# Key_LED_Buzzer.net
KiCad netlist of a schematic drawn in Altium Designer
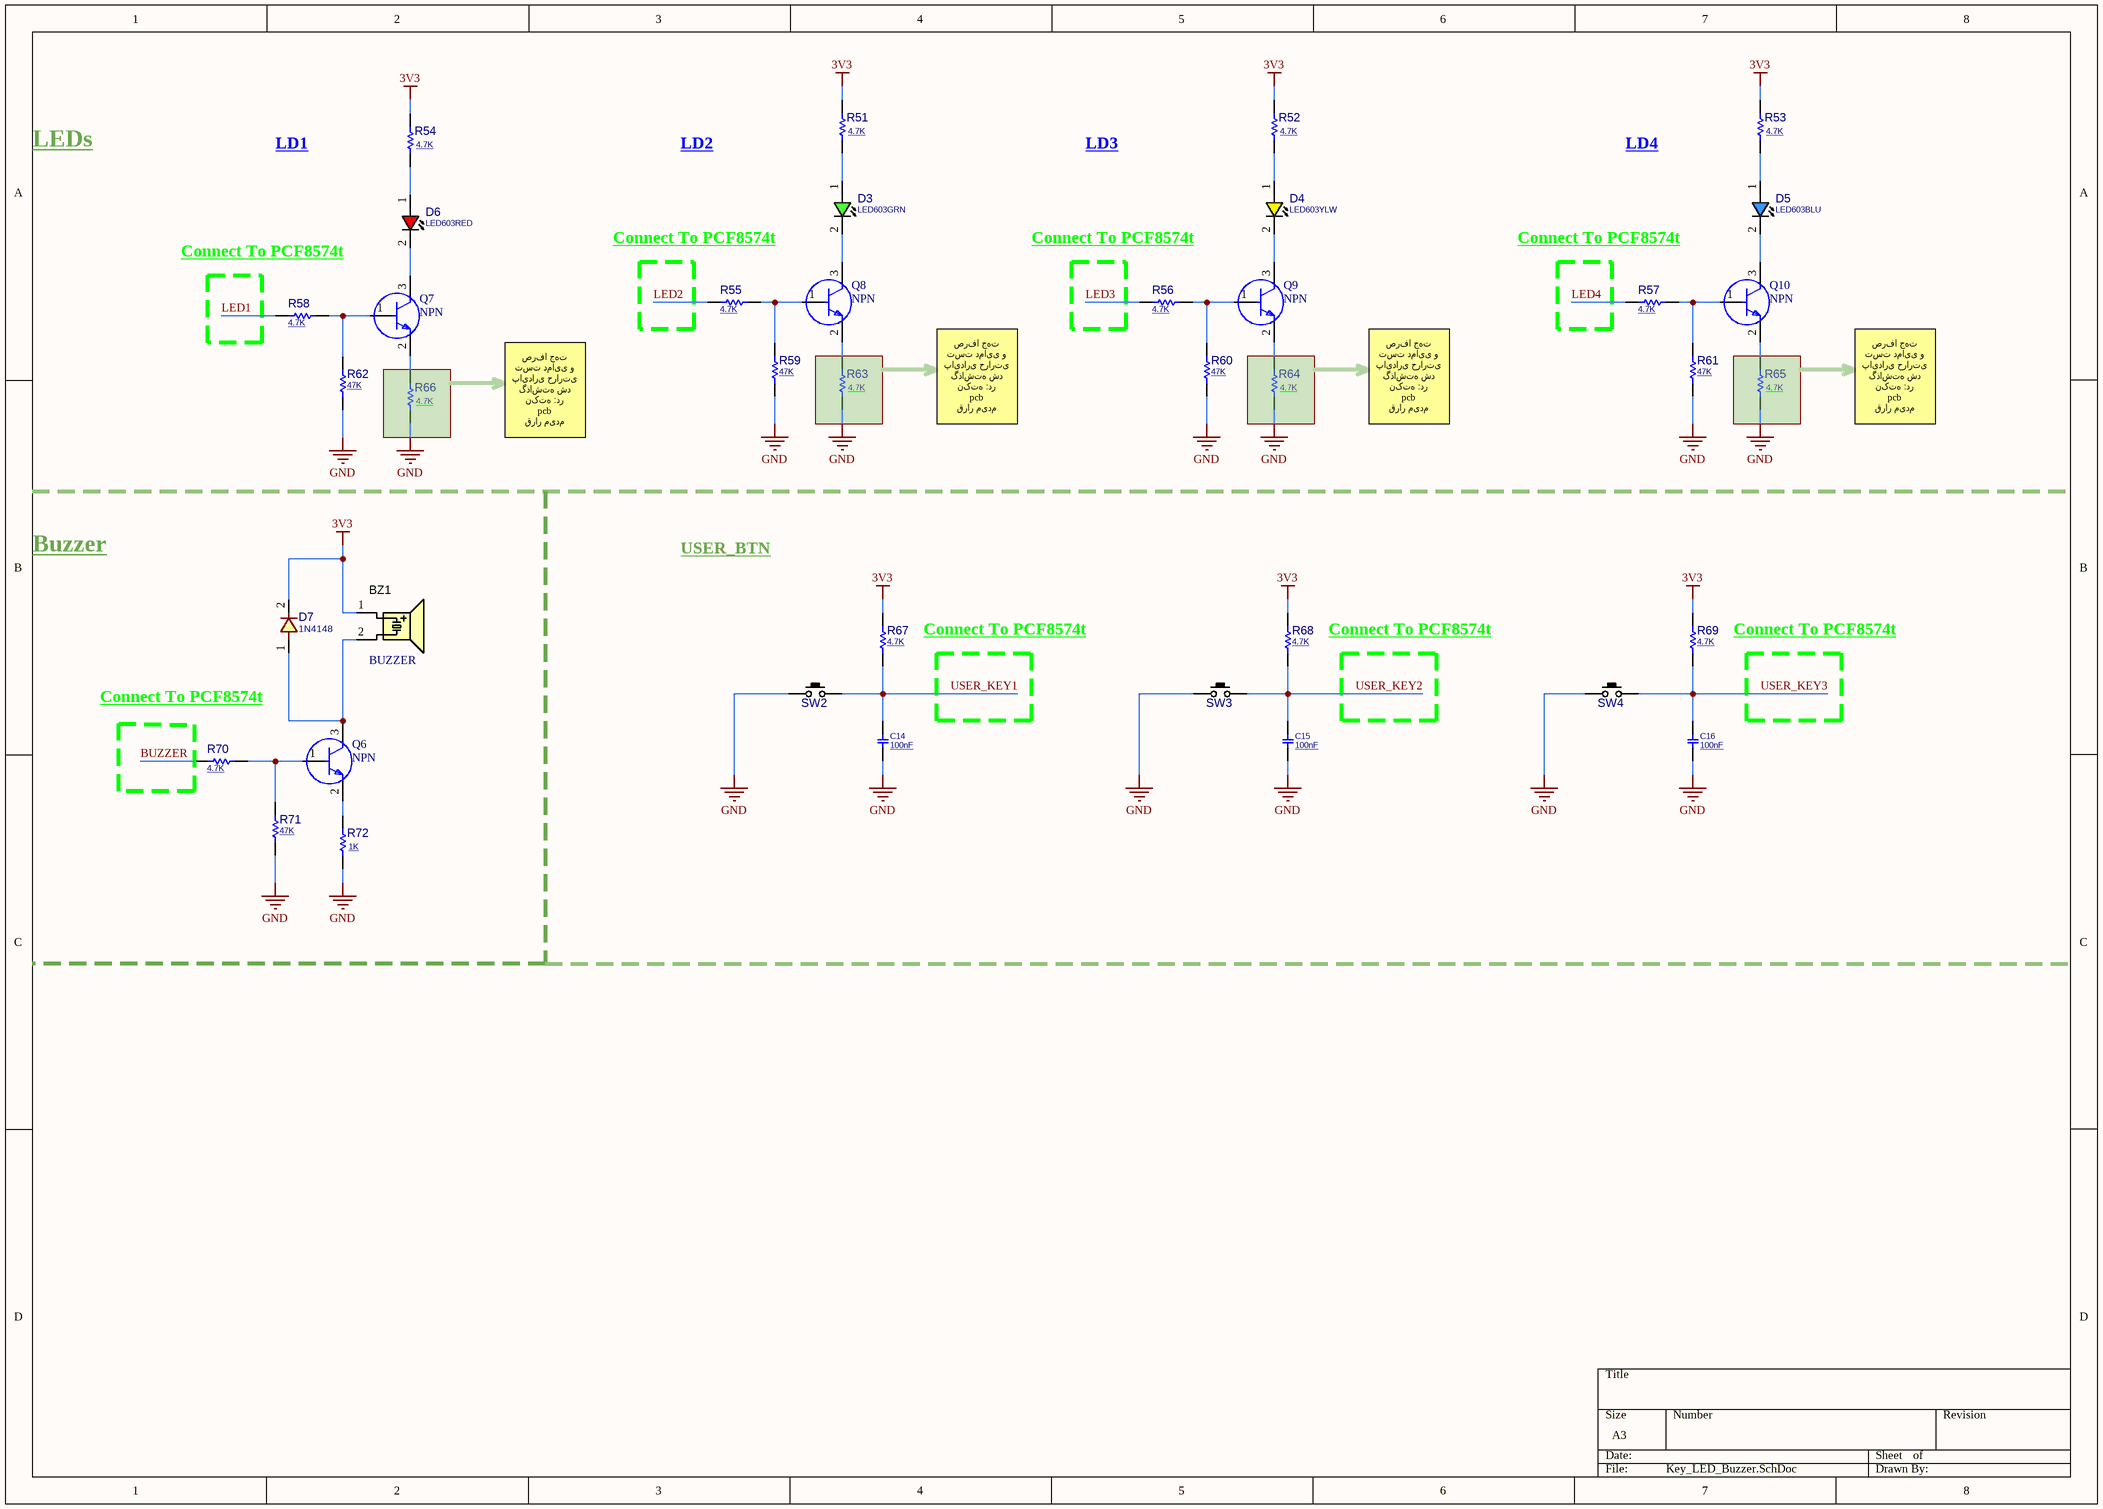
[diagram p0: Key_LED_Buzzer.SchDoc]

(export (version "E")
  (design (tool "Eeschema 10.0.6"))
  (components
    (comp (ref "BZ1")
      (value "BUZZER")
      (footprint "BZ_SMD_S8")
      (description "Buzzer, SMD, sealed 8.5x8.5x3mm LWH , 3Vp")
      (fields (field (name "MANF") "cre-sound") (field (name "MANF_P#") "LET8530BS-03L-2.7-16-R"))
      (libsource (lib "audio_mic_spk") (part "BZ_SMD_8X8X3"))
    )
    (comp (ref "C14")
      (value "100nF")
      (footprint "C0603")
      (description "CAP, MLCC, -F, -V, MATERIAL, -%, 0201")
      (fields (field (name "MANF_P#") "MANF_PART#"))
      (libsource (lib "passive_smd") (part "CAP_SMD_MLCC_0603"))
    )
    (comp (ref "C15")
      (value "100nF")
      (footprint "C0603")
      (description "CAP, MLCC, -F, -V, MATERIAL, -%, 0201")
      (fields (field (name "MANF_P#") "MANF_PART#"))
      (libsource (lib "passive_smd") (part "CAP_SMD_MLCC_0603"))
    )
    (comp (ref "C16")
      (value "100nF")
      (footprint "C0603")
      (description "CAP, MLCC, -F, -V, MATERIAL, -%, 0201")
      (fields (field (name "MANF_P#") "MANF_PART#"))
      (libsource (lib "passive_smd") (part "CAP_SMD_MLCC_0603"))
    )
    (comp (ref "D3")
      (value "LED603GRN")
      (footprint "LED0603GRN")
      (description "LED, SMD, 0603, GREEN")
      (fields (field (name "MANF") "Kingbright") (field (name "MANF_P#") "APT1608SGC"))
      (libsource (lib "led(diode)") (part "LED_SMD_0603_GRN"))
    )
    (comp (ref "D4")
      (value "LED603YLW")
      (footprint "LED0603YLW")
      (description "LED, SMD, 0603, YELLOW")
      (fields (field (name "MANF") "MANF") (field (name "MANF_P#") "MANF_PART#"))
      (libsource (lib "led(diode)") (part "LED_SMD_0603_YLW"))
    )
    (comp (ref "D5")
      (value "LED603BLU")
      (footprint "LED0603BLU")
      (description "LED, SMD, 0603, BLUE")
      (fields (field (name "MANF") "MANF") (field (name "MANF_P#") "MANF_PART#"))
      (libsource (lib "led(diode)") (part "LED_SMD_0603_BLU"))
    )
    (comp (ref "D6")
      (value "LED603RED")
      (footprint "LED0603RED")
      (description "LED, SMD, 0603, RED")
      (fields (field (name "MANF") "MANF") (field (name "MANF_P#") "MANF_PART#"))
      (libsource (lib "led(diode)") (part "LED_SMD_0603_RED"))
    )
    (comp (ref "D7")
      (value "1N4148")
      (footprint "D_SOD80")
      (description "DIODE, FAST SWTICHING, 0.3A, 0.5W")
      (fields (field (name "MANF") "MANF"))
      (libsource (lib "diode") (part "DIODE_SMD_1N4148_SOD80"))
    )
    (comp (ref "Q6")
      (value "NPN")
      (footprint "FP-SOT23-IPC_A")
      (libsource (lib "NPN-SOT-23") (part "CMP-2000-04931-2"))
    )
    (comp (ref "Q7")
      (value "NPN")
      (footprint "FP-SOT23-IPC_A")
      (libsource (lib "NPN-SOT-23") (part "CMP-2000-04931-2"))
    )
    (comp (ref "Q8")
      (value "NPN")
      (footprint "FP-SOT23-IPC_A")
      (libsource (lib "NPN-SOT-23") (part "CMP-2000-04931-2"))
    )
    (comp (ref "Q9")
      (value "NPN")
      (footprint "FP-SOT23-IPC_A")
      (libsource (lib "NPN-SOT-23") (part "CMP-2000-04931-2"))
    )
    (comp (ref "Q10")
      (value "NPN")
      (footprint "FP-SOT23-IPC_A")
      (libsource (lib "NPN-SOT-23") (part "CMP-2000-04931-2"))
    )
    (comp (ref "R51")
      (value "4.7K")
      (footprint "R0603")
      (description "RESISTOR, SMD")
      (libsource (lib "passive_smd") (part "RES_SMD"))
    )
    (comp (ref "R52")
      (value "4.7K")
      (footprint "R0603")
      (description "RESISTOR, SMD")
      (libsource (lib "passive_smd") (part "RES_SMD"))
    )
    (comp (ref "R53")
      (value "4.7K")
      (footprint "R0603")
      (description "RESISTOR, SMD")
      (libsource (lib "passive_smd") (part "RES_SMD"))
    )
    (comp (ref "R54")
      (value "4.7K")
      (footprint "R0603")
      (description "RESISTOR, SMD")
      (libsource (lib "passive_smd") (part "RES_SMD"))
    )
    (comp (ref "R55")
      (value "4.7K")
      (footprint "R0603")
      (description "RESISTOR, SMD")
      (libsource (lib "passive_smd") (part "RES_SMD"))
    )
    (comp (ref "R56")
      (value "4.7K")
      (footprint "R0603")
      (description "RESISTOR, SMD")
      (libsource (lib "passive_smd") (part "RES_SMD"))
    )
    (comp (ref "R57")
      (value "4.7K")
      (footprint "R0603")
      (description "RESISTOR, SMD")
      (libsource (lib "passive_smd") (part "RES_SMD"))
    )
    (comp (ref "R58")
      (value "4.7K")
      (footprint "R0603")
      (description "RESISTOR, SMD")
      (libsource (lib "passive_smd") (part "RES_SMD"))
    )
    (comp (ref "R59")
      (value "47K")
      (footprint "R0603")
      (description "RESISTOR, SMD")
      (libsource (lib "passive_smd") (part "RES_SMD"))
    )
    (comp (ref "R60")
      (value "47K")
      (footprint "R0603")
      (description "RESISTOR, SMD")
      (libsource (lib "passive_smd") (part "RES_SMD"))
    )
    (comp (ref "R61")
      (value "47K")
      (footprint "R0603")
      (description "RESISTOR, SMD")
      (libsource (lib "passive_smd") (part "RES_SMD"))
    )
    (comp (ref "R62")
      (value "47K")
      (footprint "R0603")
      (description "RESISTOR, SMD")
      (libsource (lib "passive_smd") (part "RES_SMD"))
    )
    (comp (ref "R63")
      (value "4.7K")
      (footprint "R0603")
      (description "RESISTOR, SMD")
      (libsource (lib "passive_smd") (part "RES_SMD"))
    )
    (comp (ref "R64")
      (value "4.7K")
      (footprint "R0603")
      (description "RESISTOR, SMD")
      (libsource (lib "passive_smd") (part "RES_SMD"))
    )
    (comp (ref "R65")
      (value "4.7K")
      (footprint "R0603")
      (description "RESISTOR, SMD")
      (libsource (lib "passive_smd") (part "RES_SMD"))
    )
    (comp (ref "R66")
      (value "4.7K")
      (footprint "R0603")
      (description "RESISTOR, SMD")
      (libsource (lib "passive_smd") (part "RES_SMD"))
    )
    (comp (ref "R67")
      (value "4.7K")
      (footprint "R0603")
      (description "RESISTOR, SMD")
      (libsource (lib "passive_smd") (part "RES_SMD"))
    )
    (comp (ref "R68")
      (value "4.7K")
      (footprint "R0603")
      (description "RESISTOR, SMD")
      (libsource (lib "passive_smd") (part "RES_SMD"))
    )
    (comp (ref "R69")
      (value "4.7K")
      (footprint "R0603")
      (description "RESISTOR, SMD")
      (libsource (lib "passive_smd") (part "RES_SMD"))
    )
    (comp (ref "R70")
      (value "4.7K")
      (footprint "R0603")
      (description "RESISTOR, SMD")
      (libsource (lib "passive_smd") (part "RES_SMD"))
    )
    (comp (ref "R71")
      (value "47K")
      (footprint "R0603")
      (description "RESISTOR, SMD")
      (libsource (lib "passive_smd") (part "RES_SMD"))
    )
    (comp (ref "R72")
      (value "1K")
      (footprint "R0603")
      (description "RESISTOR, SMD")
      (libsource (lib "passive_smd") (part "RES_SMD"))
    )
    (comp (ref "SW2")
      (value "PUSHBUTTON")
      (footprint "SWPBS_SPST_6X3X5")
      (description "SWITCH, PUSH BUTTON, TACTILE, SMD, SPST, 6X3.5X5mm")
      (fields (field (name "MANF") "ALPS") (field (name "MANF_P#") "SKQMBBE010"))
      (libsource (lib "switch_tact_PUSHB") (part "SWPBS_SPST_6X3X5"))
    )
    (comp (ref "SW3")
      (value "PUSHBUTTON")
      (footprint "SWPBS_SPST_6X3X5")
      (description "SWITCH, PUSH BUTTON, TACTILE, SMD, SPST, 6X3.5X5mm")
      (fields (field (name "MANF") "ALPS") (field (name "MANF_P#") "SKQMBBE010"))
      (libsource (lib "switch_tact_PUSHB") (part "SWPBS_SPST_6X3X5"))
    )
    (comp (ref "SW4")
      (value "PUSHBUTTON")
      (footprint "SWPBS_SPST_6X3X5")
      (description "SWITCH, PUSH BUTTON, TACTILE, SMD, SPST, 6X3.5X5mm")
      (fields (field (name "MANF") "ALPS") (field (name "MANF_P#") "SKQMBBE010"))
      (libsource (lib "switch_tact_PUSHB") (part "SWPBS_SPST_6X3X5"))
    )
  )
  (nets
    (net (code "1") (name "/BUZZER") (class "Default")
      (node (ref "R70") (pin "2") (pinfunction "2_2") (pintype "passive"))
    )
    (net (code "2") (name "/LED1") (class "Default")
      (node (ref "R58") (pin "2") (pinfunction "2_2") (pintype "passive"))
    )
    (net (code "3") (name "/LED2") (class "Default")
      (node (ref "R55") (pin "2") (pinfunction "2_2") (pintype "passive"))
    )
    (net (code "4") (name "/LED3") (class "Default")
      (node (ref "R56") (pin "2") (pinfunction "2_2") (pintype "passive"))
    )
    (net (code "5") (name "/LED4") (class "Default")
      (node (ref "R57") (pin "2") (pinfunction "2_2") (pintype "passive"))
    )
    (net (code "6") (name "/USER_KEY1") (class "Default")
      (node (ref "C14") (pin "2") (pinfunction "2_2") (pintype "passive"))
      (node (ref "R67") (pin "2") (pinfunction "2_2") (pintype "passive"))
      (node (ref "SW2") (pin "2") (pinfunction "P3_2") (pintype "passive"))
    )
    (net (code "7") (name "/USER_KEY2") (class "Default")
      (node (ref "C15") (pin "2") (pinfunction "2_2") (pintype "passive"))
      (node (ref "R68") (pin "2") (pinfunction "2_2") (pintype "passive"))
      (node (ref "SW3") (pin "2") (pinfunction "P3_2") (pintype "passive"))
    )
    (net (code "8") (name "/USER_KEY3") (class "Default")
      (node (ref "C16") (pin "2") (pinfunction "2_2") (pintype "passive"))
      (node (ref "R69") (pin "2") (pinfunction "2_2") (pintype "passive"))
      (node (ref "SW4") (pin "2") (pinfunction "P3_2") (pintype "passive"))
    )
    (net (code "9") (name "3V3") (class "Default")
      (node (ref "BZ1") (pin "1") (pinfunction "A_1") (pintype "passive"))
      (node (ref "D7") (pin "2") (pinfunction "2_2") (pintype "passive"))
      (node (ref "R51") (pin "2") (pinfunction "2_2") (pintype "passive"))
      (node (ref "R52") (pin "2") (pinfunction "2_2") (pintype "passive"))
      (node (ref "R53") (pin "2") (pinfunction "2_2") (pintype "passive"))
      (node (ref "R54") (pin "2") (pinfunction "2_2") (pintype "passive"))
      (node (ref "R67") (pin "1") (pinfunction "1_1") (pintype "passive"))
      (node (ref "R68") (pin "1") (pinfunction "1_1") (pintype "passive"))
      (node (ref "R69") (pin "1") (pinfunction "1_1") (pintype "passive"))
    )
    (net (code "10") (name "GND") (class "Default")
      (node (ref "C14") (pin "1") (pinfunction "1_1") (pintype "passive"))
      (node (ref "C15") (pin "1") (pinfunction "1_1") (pintype "passive"))
      (node (ref "C16") (pin "1") (pinfunction "1_1") (pintype "passive"))
      (node (ref "R59") (pin "2") (pinfunction "2_2") (pintype "passive"))
      (node (ref "R60") (pin "2") (pinfunction "2_2") (pintype "passive"))
      (node (ref "R61") (pin "2") (pinfunction "2_2") (pintype "passive"))
      (node (ref "R62") (pin "2") (pinfunction "2_2") (pintype "passive"))
      (node (ref "R63") (pin "1") (pinfunction "1_1") (pintype "passive"))
      (node (ref "R64") (pin "1") (pinfunction "1_1") (pintype "passive"))
      (node (ref "R65") (pin "1") (pinfunction "1_1") (pintype "passive"))
      (node (ref "R66") (pin "1") (pinfunction "1_1") (pintype "passive"))
      (node (ref "R71") (pin "2") (pinfunction "2_2") (pintype "passive"))
      (node (ref "R72") (pin "1") (pinfunction "1_1") (pintype "passive"))
      (node (ref "SW2") (pin "1") (pinfunction "P1_1") (pintype "passive"))
      (node (ref "SW3") (pin "1") (pinfunction "P1_1") (pintype "passive"))
      (node (ref "SW4") (pin "1") (pinfunction "P1_1") (pintype "passive"))
    )
    (net (code "11") (name "Net-(BZ1-B)") (class "Default")
      (node (ref "BZ1") (pin "2") (pinfunction "B_2") (pintype "passive"))
      (node (ref "D7") (pin "1") (pinfunction "1_1") (pintype "passive"))
      (node (ref "Q6") (pin "3") (pinfunction "C_3") (pintype "passive"))
    )
    (net (code "12") (name "Net-(D3-ANODE)") (class "Default")
      (node (ref "D3") (pin "1") (pinfunction "ANODE_1") (pintype "passive"))
      (node (ref "R51") (pin "1") (pinfunction "1_1") (pintype "passive"))
    )
    (net (code "13") (name "Net-(D3-CATHODE)") (class "Default")
      (node (ref "D3") (pin "2") (pinfunction "CATHODE_2") (pintype "passive"))
      (node (ref "Q8") (pin "3") (pinfunction "C_3") (pintype "passive"))
    )
    (net (code "14") (name "Net-(D4-ANODE)") (class "Default")
      (node (ref "D4") (pin "1") (pinfunction "ANODE_1") (pintype "passive"))
      (node (ref "R52") (pin "1") (pinfunction "1_1") (pintype "passive"))
    )
    (net (code "15") (name "Net-(D4-CATHODE)") (class "Default")
      (node (ref "D4") (pin "2") (pinfunction "CATHODE_2") (pintype "passive"))
      (node (ref "Q9") (pin "3") (pinfunction "C_3") (pintype "passive"))
    )
    (net (code "16") (name "Net-(D5-ANODE)") (class "Default")
      (node (ref "D5") (pin "1") (pinfunction "ANODE_1") (pintype "passive"))
      (node (ref "R53") (pin "1") (pinfunction "1_1") (pintype "passive"))
    )
    (net (code "17") (name "Net-(D5-CATHODE)") (class "Default")
      (node (ref "D5") (pin "2") (pinfunction "CATHODE_2") (pintype "passive"))
      (node (ref "Q10") (pin "3") (pinfunction "C_3") (pintype "passive"))
    )
    (net (code "18") (name "Net-(D6-ANODE)") (class "Default")
      (node (ref "D6") (pin "1") (pinfunction "ANODE_1") (pintype "passive"))
      (node (ref "R54") (pin "1") (pinfunction "1_1") (pintype "passive"))
    )
    (net (code "19") (name "Net-(D6-CATHODE)") (class "Default")
      (node (ref "D6") (pin "2") (pinfunction "CATHODE_2") (pintype "passive"))
      (node (ref "Q7") (pin "3") (pinfunction "C_3") (pintype "passive"))
    )
    (net (code "20") (name "Net-(Q6-B)") (class "Default")
      (node (ref "Q6") (pin "1") (pinfunction "B_1") (pintype "passive"))
      (node (ref "R70") (pin "1") (pinfunction "1_1") (pintype "passive"))
      (node (ref "R71") (pin "1") (pinfunction "1_1") (pintype "passive"))
    )
    (net (code "21") (name "Net-(Q6-E)") (class "Default")
      (node (ref "Q6") (pin "2") (pinfunction "E_2") (pintype "passive"))
      (node (ref "R72") (pin "2") (pinfunction "2_2") (pintype "passive"))
    )
    (net (code "22") (name "Net-(Q7-B)") (class "Default")
      (node (ref "Q7") (pin "1") (pinfunction "B_1") (pintype "passive"))
      (node (ref "R58") (pin "1") (pinfunction "1_1") (pintype "passive"))
      (node (ref "R62") (pin "1") (pinfunction "1_1") (pintype "passive"))
    )
    (net (code "23") (name "Net-(Q7-E)") (class "Default")
      (node (ref "Q7") (pin "2") (pinfunction "E_2") (pintype "passive"))
      (node (ref "R66") (pin "2") (pinfunction "2_2") (pintype "passive"))
    )
    (net (code "24") (name "Net-(Q8-B)") (class "Default")
      (node (ref "Q8") (pin "1") (pinfunction "B_1") (pintype "passive"))
      (node (ref "R55") (pin "1") (pinfunction "1_1") (pintype "passive"))
      (node (ref "R59") (pin "1") (pinfunction "1_1") (pintype "passive"))
    )
    (net (code "25") (name "Net-(Q8-E)") (class "Default")
      (node (ref "Q8") (pin "2") (pinfunction "E_2") (pintype "passive"))
      (node (ref "R63") (pin "2") (pinfunction "2_2") (pintype "passive"))
    )
    (net (code "26") (name "Net-(Q9-B)") (class "Default")
      (node (ref "Q9") (pin "1") (pinfunction "B_1") (pintype "passive"))
      (node (ref "R56") (pin "1") (pinfunction "1_1") (pintype "passive"))
      (node (ref "R60") (pin "1") (pinfunction "1_1") (pintype "passive"))
    )
    (net (code "27") (name "Net-(Q9-E)") (class "Default")
      (node (ref "Q9") (pin "2") (pinfunction "E_2") (pintype "passive"))
      (node (ref "R64") (pin "2") (pinfunction "2_2") (pintype "passive"))
    )
    (net (code "28") (name "Net-(Q10-B)") (class "Default")
      (node (ref "Q10") (pin "1") (pinfunction "B_1") (pintype "passive"))
      (node (ref "R57") (pin "1") (pinfunction "1_1") (pintype "passive"))
      (node (ref "R61") (pin "1") (pinfunction "1_1") (pintype "passive"))
    )
    (net (code "29") (name "Net-(Q10-E)") (class "Default")
      (node (ref "Q10") (pin "2") (pinfunction "E_2") (pintype "passive"))
      (node (ref "R65") (pin "2") (pinfunction "2_2") (pintype "passive"))
    )
  )
)
